# Signal_distribution.net
KiCad netlist of a schematic drawn in Altium Designer
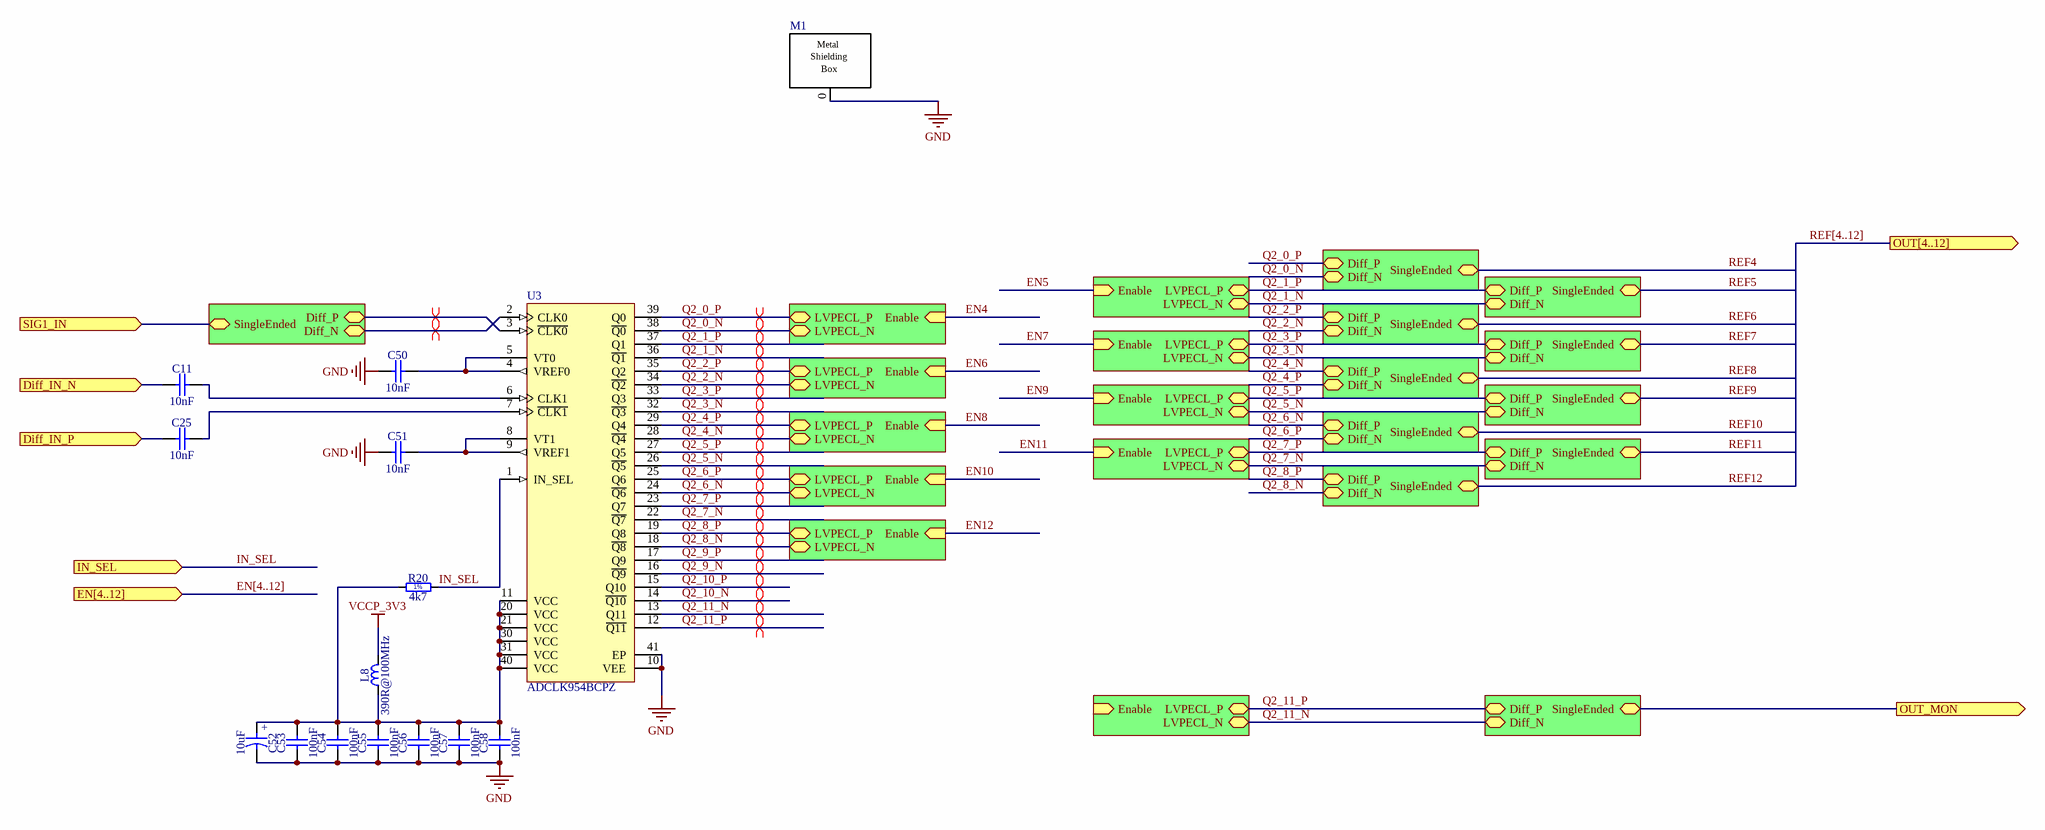
[diagram p0: Signal_distribution.SchDoc]

(export (version "E")
  (design (tool "Eeschema 10.0.6"))
  (components
    (comp (ref "C11")
      (value "10nF")
      (footprint "CAPC1005X55N")
      (description "Non-polarised capacitor")
      (fields
        (field (name "PART NUMBER") "CC0402_10NF_16V_10%_X7R")
        (field (name "VOLTAGE") "16V")
        (field (name "AUTHOR") "CERN DEM JLC")
      )
      (libsource (lib "Capacitors") (part "Capacitor - non polarized"))
    )
    (comp (ref "C25")
      (value "10nF")
      (footprint "CAPC1005X55N")
      (description "Non-polarised capacitor")
      (fields
        (field (name "PART NUMBER") "CC0402_10NF_16V_10%_X7R")
        (field (name "VOLTAGE") "16V")
        (field (name "AUTHOR") "CERN DEM JLC")
      )
      (libsource (lib "Capacitors") (part "Capacitor - non polarized"))
    )
    (comp (ref "C50")
      (value "10nF")
      (footprint "CAPC1005X55N")
      (description "Non-polarised capacitor")
      (fields
        (field (name "PART NUMBER") "CC0402_10NF_16V_10%_X7R")
        (field (name "VOLTAGE") "16V")
        (field (name "AUTHOR") "CERN DEM JLC")
      )
      (libsource (lib "Capacitors") (part "Capacitor - non polarized"))
    )
    (comp (ref "C51")
      (value "10nF")
      (footprint "CAPC1005X55N")
      (description "Non-polarised capacitor")
      (fields
        (field (name "PART NUMBER") "CC0402_10NF_16V_10%_X7R")
        (field (name "VOLTAGE") "16V")
        (field (name "AUTHOR") "CERN DEM JLC")
      )
      (libsource (lib "Capacitors") (part "Capacitor - non polarized"))
    )
    (comp (ref "C52")
      (value "10uF")
      (footprint "CAPMP3216X180N")
      (description "Polarised capacitor")
      (fields
        (field (name "PART NUMBER") "CTE3216-18_10UF_10V_10%_LESR1800")
        (field (name "VOLTAGE") "10V")
        (field (name "AUTHOR") "CERN DEM JLC")
      )
      (libsource (lib "Capacitors") (part "Capacitor - polarized"))
    )
    (comp (ref "C53")
      (value "100nF")
      (footprint "CAPC1005X55N")
      (description "Non-polarised capacitor")
      (fields
        (field (name "PART NUMBER") "CC0402_100NF_16V_10%_X7R")
        (field (name "VOLTAGE") "16V")
        (field (name "AUTHOR") "CERN DEM JLC")
      )
      (libsource (lib "Capacitors") (part "Capacitor - non polarized"))
    )
    (comp (ref "C54")
      (value "100nF")
      (footprint "CAPC1005X55N")
      (description "Non-polarised capacitor")
      (fields
        (field (name "PART NUMBER") "CC0402_100NF_16V_10%_X7R")
        (field (name "VOLTAGE") "16V")
        (field (name "AUTHOR") "CERN DEM JLC")
      )
      (libsource (lib "Capacitors") (part "Capacitor - non polarized"))
    )
    (comp (ref "C55")
      (value "100nF")
      (footprint "CAPC1005X55N")
      (description "Non-polarised capacitor")
      (fields
        (field (name "PART NUMBER") "CC0402_100NF_16V_10%_X7R")
        (field (name "VOLTAGE") "16V")
        (field (name "AUTHOR") "CERN DEM JLC")
      )
      (libsource (lib "Capacitors") (part "Capacitor - non polarized"))
    )
    (comp (ref "C56")
      (value "100nF")
      (footprint "CAPC1005X55N")
      (description "Non-polarised capacitor")
      (fields
        (field (name "PART NUMBER") "CC0402_100NF_16V_10%_X7R")
        (field (name "VOLTAGE") "16V")
        (field (name "AUTHOR") "CERN DEM JLC")
      )
      (libsource (lib "Capacitors") (part "Capacitor - non polarized"))
    )
    (comp (ref "C57")
      (value "100nF")
      (footprint "CAPC1005X55N")
      (description "Non-polarised capacitor")
      (fields
        (field (name "PART NUMBER") "CC0402_100NF_16V_10%_X7R")
        (field (name "VOLTAGE") "16V")
        (field (name "AUTHOR") "CERN DEM JLC")
      )
      (libsource (lib "Capacitors") (part "Capacitor - non polarized"))
    )
    (comp (ref "C58")
      (value "100nF")
      (footprint "CAPC1005X55N")
      (description "Non-polarised capacitor")
      (fields
        (field (name "PART NUMBER") "CC0402_100NF_16V_10%_X7R")
        (field (name "VOLTAGE") "16V")
        (field (name "AUTHOR") "CERN DEM JLC")
      )
      (libsource (lib "Capacitors") (part "Capacitor - non polarized"))
    )
    (comp (ref "L8")
      (value "390R@100MHz")
      (footprint "INDC1608X95N")
      (description "Inductor")
      (fields
        (field (name "PART NUMBER") "IND0603_TDK_MPZ1608R391A")
        (field (name "POWER") "1.2A")
        (field (name "AUTHOR") "CERN DEM JLC")
      )
      (libsource (lib "Inductors & Transformers") (part "Inductor"))
    )
    (comp (ref "M1")
      (value "Shield")
      (footprint "BMI-S-202-F")
      (description "STANDARD SURFACE MOUNT SHIELD  TWO-PIECE PART NO. BMI-S-202")
      (fields (field (name "MANUFACTURER") "Laird Technologies"))
      (libsource (lib "elementy_bierne") (part "BMI-S-202-F"))
    )
    (comp (ref "R20")
      (value "4k7")
      (footprint "RESC1005X40N")
      (description "Resistor - 1%")
      (fields
        (field (name "PART NUMBER") "R0402_4K7_1%_0.0625W_100PPM")
        (field (name "POWER") "0.0625W")
        (field (name "AUTHOR") "CERN DEM JLC")
      )
      (libsource (lib "Resistors") (part "Resistor - 1%"))
    )
    (comp (ref "U3")
      (value "ADCLK954BCPZ")
      (footprint "ADI-CP-40-8_M")
      (fields (field (name "MANUFACTURER") "Analog Devices"))
      (libsource (lib "Altium Content Vault") (part "ADI-ADCLK954-CP-40-8"))
    )
  )
  (nets
    (net (code "1") (name "/Diff_IN_N") (class "Default")
      (node (ref "C11") (pin "1") (pinfunction "1_1") (pintype "passive"))
    )
    (net (code "2") (name "/Diff_IN_P") (class "Default")
      (node (ref "C25") (pin "1") (pinfunction "1_1") (pintype "passive"))
    )
    (net (code "3") (name "/Diff_N") (class "Default")
      (node (ref "U3") (pin "2") (pinfunction "CLK0_2") (pintype "input"))
    )
    (net (code "4") (name "/Diff_P") (class "Default")
      (node (ref "U3") (pin "3") (pinfunction "~{CLK0}_3") (pintype "input"))
    )
    (net (code "16") (name "/IN_SEL") (class "Default")
      (node (ref "R20") (pin "2") (pinfunction "2_2") (pintype "passive"))
      (node (ref "U3") (pin "1") (pinfunction "IN_SEL_1") (pintype "input"))
    )
    (net (code "18") (name "/Q2_0_N") (class "Default")
      (node (ref "U3") (pin "38") (pinfunction "~{Q0}_38") (pintype "open_emitter"))
    )
    (net (code "19") (name "/Q2_0_P") (class "Default")
      (node (ref "U3") (pin "39") (pinfunction "Q0_39") (pintype "open_emitter"))
    )
    (net (code "20") (name "/Q2_1_N") (class "Default")
      (node (ref "U3") (pin "36") (pinfunction "~{Q1}_36") (pintype "open_emitter"))
    )
    (net (code "21") (name "/Q2_1_P") (class "Default")
      (node (ref "U3") (pin "37") (pinfunction "Q1_37") (pintype "open_emitter"))
    )
    (net (code "22") (name "/Q2_2_N") (class "Default")
      (node (ref "U3") (pin "34") (pinfunction "~{Q2}_34") (pintype "open_emitter"))
    )
    (net (code "23") (name "/Q2_2_P") (class "Default")
      (node (ref "U3") (pin "35") (pinfunction "Q2_35") (pintype "open_emitter"))
    )
    (net (code "24") (name "/Q2_3_N") (class "Default")
      (node (ref "U3") (pin "32") (pinfunction "~{Q3}_32") (pintype "open_emitter"))
    )
    (net (code "25") (name "/Q2_3_P") (class "Default")
      (node (ref "U3") (pin "33") (pinfunction "Q3_33") (pintype "open_emitter"))
    )
    (net (code "26") (name "/Q2_4_N") (class "Default")
      (node (ref "U3") (pin "28") (pinfunction "~{Q4}_28") (pintype "open_emitter"))
    )
    (net (code "27") (name "/Q2_4_P") (class "Default")
      (node (ref "U3") (pin "29") (pinfunction "Q4_29") (pintype "open_emitter"))
    )
    (net (code "28") (name "/Q2_5_N") (class "Default")
      (node (ref "U3") (pin "26") (pinfunction "~{Q5}_26") (pintype "open_emitter"))
    )
    (net (code "29") (name "/Q2_5_P") (class "Default")
      (node (ref "U3") (pin "27") (pinfunction "Q5_27") (pintype "open_emitter"))
    )
    (net (code "30") (name "/Q2_6_N") (class "Default")
      (node (ref "U3") (pin "24") (pinfunction "~{Q6}_24") (pintype "open_emitter"))
    )
    (net (code "31") (name "/Q2_6_P") (class "Default")
      (node (ref "U3") (pin "25") (pinfunction "Q6_25") (pintype "open_emitter"))
    )
    (net (code "32") (name "/Q2_7_N") (class "Default")
      (node (ref "U3") (pin "22") (pinfunction "~{Q7}_22") (pintype "open_emitter"))
    )
    (net (code "33") (name "/Q2_7_P") (class "Default")
      (node (ref "U3") (pin "23") (pinfunction "Q7_23") (pintype "open_emitter"))
    )
    (net (code "34") (name "/Q2_8_N") (class "Default")
      (node (ref "U3") (pin "18") (pinfunction "~{Q8}_18") (pintype "open_emitter"))
    )
    (net (code "35") (name "/Q2_8_P") (class "Default")
      (node (ref "U3") (pin "19") (pinfunction "Q8_19") (pintype "open_emitter"))
    )
    (net (code "36") (name "/Q2_9_N") (class "Default")
      (node (ref "U3") (pin "16") (pinfunction "~{Q9}_16") (pintype "open_emitter"))
    )
    (net (code "37") (name "/Q2_9_P") (class "Default")
      (node (ref "U3") (pin "17") (pinfunction "Q9_17") (pintype "open_emitter"))
    )
    (net (code "38") (name "/Q2_10_N") (class "Default")
      (node (ref "U3") (pin "14") (pinfunction "~{Q10}_14") (pintype "open_emitter"))
    )
    (net (code "39") (name "/Q2_10_P") (class "Default")
      (node (ref "U3") (pin "15") (pinfunction "Q10_15") (pintype "open_emitter"))
    )
    (net (code "40") (name "/Q2_11_N") (class "Default")
      (node (ref "U3") (pin "13") (pinfunction "Q11_13") (pintype "open_emitter"))
    )
    (net (code "41") (name "/Q2_11_P") (class "Default")
      (node (ref "U3") (pin "12") (pinfunction "~{Q11}_12") (pintype "open_emitter"))
    )
    (net (code "53") (name "GND") (class "Default")
      (node (ref "C50") (pin "1") (pinfunction "1_1") (pintype "passive"))
      (node (ref "C51") (pin "1") (pinfunction "1_1") (pintype "passive"))
      (node (ref "C52") (pin "2") (pinfunction "2_2") (pintype "passive"))
      (node (ref "C53") (pin "1") (pinfunction "1_1") (pintype "passive"))
      (node (ref "C54") (pin "1") (pinfunction "1_1") (pintype "passive"))
      (node (ref "C55") (pin "1") (pinfunction "1_1") (pintype "passive"))
      (node (ref "C56") (pin "1") (pinfunction "1_1") (pintype "passive"))
      (node (ref "C57") (pin "1") (pinfunction "1_1") (pintype "passive"))
      (node (ref "C58") (pin "1") (pinfunction "1_1") (pintype "passive"))
      (node (ref "M1") (pin "0") (pinfunction "SHIELD_0") (pintype "passive"))
      (node (ref "U3") (pin "10") (pinfunction "VEE_10") (pintype "power_in"))
      (node (ref "U3") (pin "41") (pinfunction "EP_41") (pintype "power_in"))
    )
    (net (code "54") (name "Net-(C52-Pad1)") (class "Default")
      (node (ref "C52") (pin "1") (pinfunction "1_1") (pintype "passive"))
      (node (ref "C53") (pin "2") (pinfunction "2_2") (pintype "passive"))
      (node (ref "C54") (pin "2") (pinfunction "2_2") (pintype "passive"))
      (node (ref "C55") (pin "2") (pinfunction "2_2") (pintype "passive"))
      (node (ref "C56") (pin "2") (pinfunction "2_2") (pintype "passive"))
      (node (ref "C57") (pin "2") (pinfunction "2_2") (pintype "passive"))
      (node (ref "C58") (pin "2") (pinfunction "2_2") (pintype "passive"))
      (node (ref "L8") (pin "1") (pinfunction "1_1") (pintype "passive"))
      (node (ref "R20") (pin "1") (pinfunction "1_1") (pintype "passive"))
      (node (ref "U3") (pin "11") (pinfunction "VCC_11") (pintype "power_in"))
      (node (ref "U3") (pin "20") (pinfunction "VCC_20") (pintype "power_in"))
      (node (ref "U3") (pin "21") (pinfunction "VCC_21") (pintype "power_in"))
      (node (ref "U3") (pin "30") (pinfunction "VCC_30") (pintype "power_in"))
      (node (ref "U3") (pin "31") (pinfunction "VCC_31") (pintype "power_in"))
      (node (ref "U3") (pin "40") (pinfunction "VCC_40") (pintype "power_in"))
    )
    (net (code "55") (name "Net-(U3-CLK1)") (class "Default")
      (node (ref "C11") (pin "2") (pinfunction "2_2") (pintype "passive"))
      (node (ref "U3") (pin "6") (pinfunction "CLK1_6") (pintype "input"))
    )
    (net (code "56") (name "Net-(U3-VREF0)") (class "Default")
      (node (ref "C50") (pin "2") (pinfunction "2_2") (pintype "passive"))
      (node (ref "U3") (pin "4") (pinfunction "VREF0_4") (pintype "output"))
      (node (ref "U3") (pin "5") (pinfunction "VT0_5") (pintype "passive"))
    )
    (net (code "57") (name "Net-(U3-VREF1)") (class "Default")
      (node (ref "C51") (pin "2") (pinfunction "2_2") (pintype "passive"))
      (node (ref "U3") (pin "8") (pinfunction "VT1_8") (pintype "passive"))
      (node (ref "U3") (pin "9") (pinfunction "VREF1_9") (pintype "output"))
    )
    (net (code "58") (name "Net-(U3-~{CLK1})") (class "Default")
      (node (ref "C25") (pin "2") (pinfunction "2_2") (pintype "passive"))
      (node (ref "U3") (pin "7") (pinfunction "~{CLK1}_7") (pintype "input"))
    )
    (net (code "59") (name "VCCP_3V3") (class "Default")
      (node (ref "L8") (pin "2") (pinfunction "2_2") (pintype "passive"))
    )
  )
)
